# SensorPlatformV3.net
KiCad netlist of a schematic drawn in Altium Designer
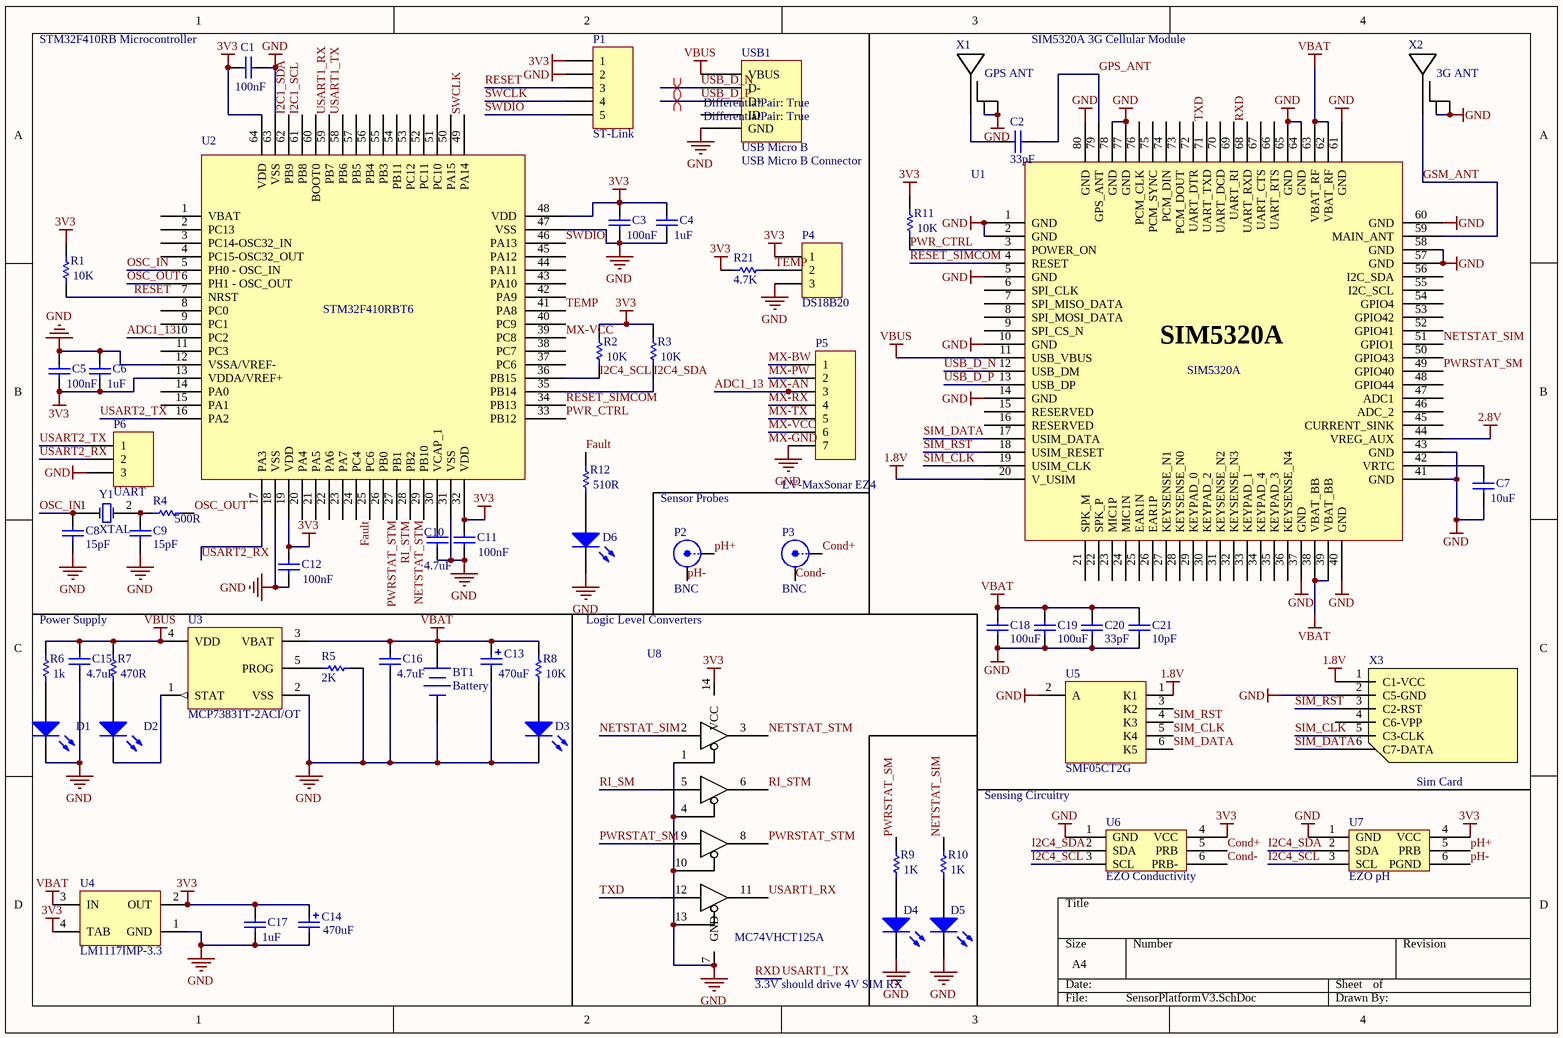
[diagram p0: SensorPlatformV3.SchDoc]

(export (version "E")
  (design (tool "Eeschema 10.0.6"))
  (components
    (comp (ref "BT1")
      (value "Battery")
      (footprint "BAT-2")
      (description "Multicell Battery")
      (fields (field (name "PUBLISHER") "Altium Limited"))
      (libsource (lib "Miscellaneous Devices") (part "Battery"))
    )
    (comp (ref "C1")
      (value "100nF")
      (footprint "1608[0603]")
      (description "Capacitor")
      (fields (field (name "Comment") "Cap") (field (name "PUBLISHER") "Altium Limited"))
      (libsource (lib "Miscellaneous Devices") (part "Cap"))
    )
    (comp (ref "C2")
      (value "33pF")
      (footprint "1608[0603]")
      (description "Capacitor")
      (fields (field (name "Comment") "Cap") (field (name "PUBLISHER") "Altium Limited"))
      (libsource (lib "Miscellaneous Devices") (part "Cap"))
    )
    (comp (ref "C3")
      (value "100nF")
      (footprint "1608[0603]")
      (description "Capacitor")
      (fields (field (name "Comment") "Cap") (field (name "PUBLISHER") "Altium Limited"))
      (libsource (lib "Miscellaneous Devices") (part "Cap"))
    )
    (comp (ref "C4")
      (value "1uF")
      (footprint "1608[0603]")
      (description "Capacitor")
      (fields (field (name "Comment") "Cap") (field (name "PUBLISHER") "Altium Limited"))
      (libsource (lib "Miscellaneous Devices") (part "Cap"))
    )
    (comp (ref "C5")
      (value "100nF")
      (footprint "1608[0603]")
      (description "Capacitor")
      (fields (field (name "Comment") "Cap") (field (name "PUBLISHER") "Altium Limited"))
      (libsource (lib "Miscellaneous Devices") (part "Cap"))
    )
    (comp (ref "C6")
      (value "1uF")
      (footprint "1608[0603]")
      (description "Capacitor")
      (fields (field (name "Comment") "Cap") (field (name "PUBLISHER") "Altium Limited"))
      (libsource (lib "Miscellaneous Devices") (part "Cap"))
    )
    (comp (ref "C7")
      (value "10uF")
      (footprint "1608[0603]")
      (description "Capacitor")
      (fields (field (name "Comment") "Cap") (field (name "PUBLISHER") "Altium Limited"))
      (libsource (lib "Miscellaneous Devices") (part "Cap"))
    )
    (comp (ref "C8")
      (value "15pF")
      (footprint "1608[0603]")
      (description "Capacitor")
      (fields (field (name "Comment") "Cap") (field (name "PUBLISHER") "Altium Limited"))
      (libsource (lib "Miscellaneous Devices") (part "Cap"))
    )
    (comp (ref "C9")
      (value "15pF")
      (footprint "1608[0603]")
      (description "Capacitor")
      (fields (field (name "Comment") "Cap") (field (name "PUBLISHER") "Altium Limited"))
      (libsource (lib "Miscellaneous Devices") (part "Cap"))
    )
    (comp (ref "C10")
      (value "4.7uF")
      (footprint "1608[0603]")
      (description "Capacitor")
      (fields (field (name "Comment") "Cap") (field (name "PUBLISHER") "Altium Limited"))
      (libsource (lib "Miscellaneous Devices") (part "Cap"))
    )
    (comp (ref "C11")
      (value "100nF")
      (footprint "1608[0603]")
      (description "Capacitor")
      (fields (field (name "Comment") "Cap") (field (name "PUBLISHER") "Altium Limited"))
      (libsource (lib "Miscellaneous Devices") (part "Cap"))
    )
    (comp (ref "C12")
      (value "100nF")
      (footprint "1608[0603]")
      (description "Capacitor")
      (fields (field (name "Comment") "Cap") (field (name "PUBLISHER") "Altium Limited"))
      (libsource (lib "Miscellaneous Devices") (part "Cap"))
    )
    (comp (ref "C13")
      (value "470uF")
      (footprint "CAPAE9983X105M")
      (description "Polarized Capacitor (Axial)")
      (fields (field (name "Comment") "Cap Pol2") (field (name "PUBLISHER") "Altium Limited"))
      (libsource (lib "Miscellaneous Devices") (part "Cap Pol2"))
    )
    (comp (ref "C14")
      (value "470uF")
      (footprint "CAPAE9983X105M")
      (description "Polarized Capacitor (Axial)")
      (fields (field (name "Comment") "Cap Pol2") (field (name "PUBLISHER") "Altium Limited"))
      (libsource (lib "Miscellaneous Devices") (part "Cap Pol2"))
    )
    (comp (ref "C15")
      (value "4.7uF")
      (footprint "1608[0603]")
      (description "Capacitor")
      (fields (field (name "Comment") "Cap") (field (name "PUBLISHER") "Altium Limited"))
      (libsource (lib "Miscellaneous Devices") (part "Cap"))
    )
    (comp (ref "C16")
      (value "4.7uF")
      (footprint "1608[0603]")
      (description "Capacitor")
      (fields (field (name "Comment") "Cap") (field (name "PUBLISHER") "Altium Limited"))
      (libsource (lib "Miscellaneous Devices") (part "Cap"))
    )
    (comp (ref "C17")
      (value "1uF")
      (footprint "1608[0603]")
      (description "Capacitor")
      (fields (field (name "Comment") "Cap") (field (name "PUBLISHER") "Altium Limited"))
      (libsource (lib "Miscellaneous Devices") (part "Cap"))
    )
    (comp (ref "C18")
      (value "100uF")
      (footprint "1608[0603]")
      (description "Capacitor")
      (fields (field (name "Comment") "Cap") (field (name "PUBLISHER") "Altium Limited"))
      (libsource (lib "Miscellaneous Devices") (part "Cap"))
    )
    (comp (ref "C19")
      (value "100uF")
      (footprint "1608[0603]")
      (description "Capacitor")
      (fields (field (name "Comment") "Cap") (field (name "PUBLISHER") "Altium Limited"))
      (libsource (lib "Miscellaneous Devices") (part "Cap"))
    )
    (comp (ref "C20")
      (value "33pF")
      (footprint "1608[0603]")
      (description "Capacitor")
      (fields (field (name "Comment") "Cap") (field (name "PUBLISHER") "Altium Limited"))
      (libsource (lib "Miscellaneous Devices") (part "Cap"))
    )
    (comp (ref "C21")
      (value "10pF")
      (footprint "1608[0603]")
      (description "Capacitor")
      (fields (field (name "Comment") "Cap") (field (name "PUBLISHER") "Altium Limited"))
      (libsource (lib "Miscellaneous Devices") (part "Cap"))
    )
    (comp (ref "D1")
      (value "USB")
      (footprint "1608[0603]")
      (description "Typical INFRARED GaAs LED")
      (fields (field (name "PUBLISHER") "Altium Limited"))
      (libsource (lib "Miscellaneous Devices") (part "LED0"))
    )
    (comp (ref "D2")
      (value "Ch")
      (footprint "1608[0603]")
      (description "Typical INFRARED GaAs LED")
      (fields (field (name "PUBLISHER") "Altium Limited"))
      (libsource (lib "Miscellaneous Devices") (part "LED0"))
    )
    (comp (ref "D3")
      (value "Bt")
      (footprint "1608[0603]")
      (description "Typical INFRARED GaAs LED")
      (fields (field (name "PUBLISHER") "Altium Limited"))
      (libsource (lib "Miscellaneous Devices") (part "LED0"))
    )
    (comp (ref "D4")
      (value "PWRSTAT")
      (footprint "1608[0603]")
      (description "Typical INFRARED GaAs LED")
      (fields (field (name "PUBLISHER") "Altium Limited"))
      (libsource (lib "Miscellaneous Devices") (part "LED0"))
    )
    (comp (ref "D5")
      (value "NETSTAT")
      (footprint "1608[0603]")
      (description "Typical INFRARED GaAs LED")
      (fields (field (name "PUBLISHER") "Altium Limited"))
      (libsource (lib "Miscellaneous Devices") (part "LED0"))
    )
    (comp (ref "D6")
      (value "Fault")
      (footprint "1608[0603]")
      (description "Typical INFRARED GaAs LED")
      (fields (field (name "PUBLISHER") "Altium Limited"))
      (libsource (lib "Miscellaneous Devices") (part "LED0"))
    )
    (comp (ref "P1")
      (value "ST-Link")
      (footprint "HDR1X5")
      (description "Header, 5-Pin")
      (fields (field (name "PUBLISHER") "Altium Limited"))
      (libsource (lib "Miscellaneous Connectors") (part "Header 5"))
    )
    (comp (ref "P2")
      (value "BNC")
      (footprint "BNC Connector")
      (description "BNC Elbow Connector")
      (fields (field (name "PUBLISHER") "Altium Limited"))
      (libsource (lib "Miscellaneous Connectors") (part "BNC"))
    )
    (comp (ref "P3")
      (value "BNC")
      (footprint "BNC Connector")
      (description "BNC Elbow Connector")
      (fields (field (name "PUBLISHER") "Altium Limited"))
      (libsource (lib "Miscellaneous Connectors") (part "BNC"))
    )
    (comp (ref "P4")
      (value "DS18B20")
      (footprint "HDR1X3")
      (description "Header, 3-Pin")
      (fields (field (name "PUBLISHER") "Altium Limited"))
      (libsource (lib "Miscellaneous Connectors") (part "Header 3"))
    )
    (comp (ref "P5")
      (value "LV-MaxSonar EZ4")
      (footprint "HDR1X7")
      (description "Header, 7-Pin")
      (fields (field (name "PUBLISHER") "Altium Limited"))
      (libsource (lib "Miscellaneous Connectors") (part "Header 7"))
    )
    (comp (ref "P6")
      (value "UART")
      (footprint "HDR1X3")
      (description "Header, 3-Pin")
      (fields (field (name "PUBLISHER") "Altium Limited"))
      (libsource (lib "Miscellaneous Connectors") (part "Header 3"))
    )
    (comp (ref "R1")
      (value "10K")
      (footprint "1608[0603]")
      (description "Resistor")
      (fields (field (name "Comment") "Res1") (field (name "PUBLISHER") "Altium Limited"))
      (libsource (lib "Miscellaneous Devices") (part "Res1"))
    )
    (comp (ref "R2")
      (value "10K")
      (footprint "1608[0603]")
      (description "Resistor")
      (fields (field (name "Comment") "Res1") (field (name "PUBLISHER") "Altium Limited"))
      (libsource (lib "Miscellaneous Devices") (part "Res1"))
    )
    (comp (ref "R3")
      (value "10K")
      (footprint "1608[0603]")
      (description "Resistor")
      (fields (field (name "Comment") "Res1") (field (name "PUBLISHER") "Altium Limited"))
      (libsource (lib "Miscellaneous Devices") (part "Res1"))
    )
    (comp (ref "R4")
      (value "500R")
      (footprint "1608[0603]")
      (description "Resistor")
      (fields (field (name "Comment") "Res1") (field (name "PUBLISHER") "Altium Limited"))
      (libsource (lib "Miscellaneous Devices") (part "Res1"))
    )
    (comp (ref "R5")
      (value "2K")
      (footprint "1608[0603]")
      (description "Resistor")
      (fields (field (name "Comment") "Res1") (field (name "PUBLISHER") "Altium Limited"))
      (libsource (lib "Miscellaneous Devices") (part "Res1"))
    )
    (comp (ref "R6")
      (value "1k")
      (footprint "1608[0603]")
      (description "Resistor")
      (fields (field (name "Comment") "Res1") (field (name "PUBLISHER") "Altium Limited"))
      (libsource (lib "Miscellaneous Devices") (part "Res1"))
    )
    (comp (ref "R7")
      (value "470R")
      (footprint "1608[0603]")
      (description "Resistor")
      (fields (field (name "Comment") "Res1") (field (name "PUBLISHER") "Altium Limited"))
      (libsource (lib "Miscellaneous Devices") (part "Res1"))
    )
    (comp (ref "R8")
      (value "10K")
      (footprint "1608[0603]")
      (description "Resistor")
      (fields (field (name "Comment") "Res1") (field (name "PUBLISHER") "Altium Limited"))
      (libsource (lib "Miscellaneous Devices") (part "Res1"))
    )
    (comp (ref "R9")
      (value "1K")
      (footprint "1608[0603]")
      (description "Resistor")
      (fields (field (name "Comment") "Res1") (field (name "PUBLISHER") "Altium Limited"))
      (libsource (lib "Miscellaneous Devices") (part "Res1"))
    )
    (comp (ref "R10")
      (value "1K")
      (footprint "1608[0603]")
      (description "Resistor")
      (fields (field (name "Comment") "Res1") (field (name "PUBLISHER") "Altium Limited"))
      (libsource (lib "Miscellaneous Devices") (part "Res1"))
    )
    (comp (ref "R11")
      (value "10K")
      (footprint "1608[0603]")
      (description "Resistor")
      (fields (field (name "Comment") "Res1") (field (name "PUBLISHER") "Altium Limited"))
      (libsource (lib "Miscellaneous Devices") (part "Res1"))
    )
    (comp (ref "R12")
      (value "510R")
      (footprint "1608[0603]")
      (description "Resistor")
      (fields (field (name "Comment") "Res1") (field (name "PUBLISHER") "Altium Limited"))
      (libsource (lib "Miscellaneous Devices") (part "Res1"))
    )
    (comp (ref "R21")
      (value "4.7K")
      (footprint "1608[0603]")
      (description "Resistor")
      (fields (field (name "Comment") "Res1") (field (name "PUBLISHER") "Altium Limited"))
      (libsource (lib "Miscellaneous Devices") (part "Res1"))
    )
    (comp (ref "U1")
      (value "SIM5320A")
      (footprint "SIM5320A")
      (libsource (lib "WillsSchematicLibrary") (part "SIM5320A"))
    )
    (comp (ref "U2")
      (value "STM32F410RBT6")
      (footprint "STM32F410RBT6")
      (libsource (lib "WillsSchematicLibrary") (part "STM32F410RBT6"))
    )
    (comp (ref "U3")
      (value "MCP73831T-2ACI/OT")
      (footprint "SOT-23-OT5_N")
      (fields (field (name "MANUFACTURER") "Microchip"))
      (libsource (lib "Microchip Power Management Battery Management") (part "MCP73831T-2ACI/OT"))
    )
    (comp (ref "U4")
      (value "LM1117IMP-3.3")
      (footprint "MP04A_N")
      (description "800mA Low-Dropout Linear Regulator, 4-pin SOT-223")
      (fields (field (name "MANUFACTURER") "National Semiconductor"))
      (libsource (lib "National Semiconductor LDO") (part "LM1117IMP-3.3"))
    )
    (comp (ref "U5")
      (value "SMF05CT2G")
      (footprint "ONSC-SC70-6-419B-02_W_V")
      (description "5-Line Transient Voltage Suppressor Array, 6-Pin SC70, Pb-Free, Tape and Reel")
      (fields (field (name "MANUFACTURER") "On Semiconductor"))
      (libsource (lib "ON Semi Transient Voltage Suppressors (TVS)") (part "SMF05CT2G"))
    )
    (comp (ref "U6")
      (value "EZO Conductivity")
      (footprint "EZO Conductivity (No Writing)")
      (libsource (lib "WillsSchematicLibrary") (part "EZO Conductivity"))
    )
    (comp (ref "U7")
      (value "EZO pH")
      (footprint "EZO pH Duplicate")
      (libsource (lib "WillsSchematicLibrary") (part "EZO pH"))
    )
    (comp (ref "U8")
      (value "MC74VHCT125A")
      (footprint "TSSOP-14")
      (libsource (lib "WillsSchematicLibrary") (part "MC74VHCT125A"))
    )
    (comp (ref "USB1")
      (value "USB Micro B Connector")
      (footprint "USB Micro B Connector")
      (libsource (lib "WillsSchematicLibrary") (part "USB Micro B Connector"))
    )
    (comp (ref "X1")
      (value "GPS ANT")
      (footprint "UFL Connector")
      (libsource (lib "WillsSchematicLibrary") (part "UFL Antenna"))
    )
    (comp (ref "X2")
      (value "3G ANT")
      (footprint "UFL Connector")
      (libsource (lib "WillsSchematicLibrary") (part "UFL Antenna"))
    )
    (comp (ref "X3")
      (value "Sim Card")
      (footprint "Sim Card")
      (libsource (lib "WillsSchematicLibrary") (part "SIMCARD"))
    )
    (comp (ref "Y1")
      (value "XTAL")
      (footprint "16MHz Clock")
      (description "Crystal Oscillator")
      (fields (field (name "PUBLISHER") "Altium Limited"))
      (libsource (lib "Miscellaneous Devices") (part "XTAL"))
    )
  )
  (nets
    (net (code "1") (name "/ADC1_13") (class "Default")
      (node (ref "P5") (pin "3") (pinfunction "3_3") (pintype "passive"))
      (node (ref "U2") (pin "10") (pinfunction "PC2_10") (pintype "passive"))
    )
    (net (code "2") (name "/Cond+") (class "Default")
      (node (ref "P3") (pin "1") (pinfunction "X_1") (pintype "passive"))
      (node (ref "U6") (pin "5") (pinfunction "PRB_5") (pintype "passive"))
    )
    (net (code "3") (name "/Cond-") (class "Default")
      (node (ref "P3") (pin "2") (pinfunction "Y_2") (pintype "passive"))
      (node (ref "U6") (pin "6") (pinfunction "PRB-_6") (pintype "passive"))
    )
    (net (code "4") (name "/Fault") (class "Default")
      (node (ref "R12") (pin "2") (pinfunction "2_2") (pintype "passive"))
      (node (ref "U2") (pin "24") (pinfunction "PC4_24") (pintype "passive"))
    )
    (net (code "5") (name "/GPS_ANT") (class "Default")
      (node (ref "C2") (pin "1") (pinfunction "1_1") (pintype "passive"))
      (node (ref "U1") (pin "79") (pinfunction "GPS_ANT_79") (pintype "passive"))
    )
    (net (code "6") (name "/GSM_ANT") (class "Default")
      (node (ref "U1") (pin "59") (pinfunction "MAIN_ANT_59") (pintype "passive"))
      (node (ref "X2") (pin "1") (pinfunction "SIG_1") (pintype "passive"))
    )
    (net (code "7") (name "/I2C1_SCL") (class "Default")
      (node (ref "U2") (pin "61") (pinfunction "PB8_61") (pintype "passive"))
    )
    (net (code "8") (name "/I2C1_SDA") (class "Default")
      (node (ref "U2") (pin "62") (pinfunction "PB9_62") (pintype "passive"))
    )
    (net (code "9") (name "/I2C4_SCL") (class "Default")
      (node (ref "R2") (pin "1") (pinfunction "1_1") (pintype "passive"))
      (node (ref "U2") (pin "36") (pinfunction "PB15_36") (pintype "passive"))
      (node (ref "U6") (pin "3") (pinfunction "SCL_3") (pintype "passive"))
      (node (ref "U7") (pin "3") (pinfunction "SCL_3") (pintype "passive"))
    )
    (net (code "10") (name "/I2C4_SDA") (class "Default")
      (node (ref "R3") (pin "1") (pinfunction "1_1") (pintype "passive"))
      (node (ref "U2") (pin "35") (pinfunction "PB14_35") (pintype "passive"))
      (node (ref "U6") (pin "2") (pinfunction "SDA_2") (pintype "passive"))
      (node (ref "U7") (pin "2") (pinfunction "SDA_2") (pintype "passive"))
    )
    (net (code "11") (name "/MX-BW") (class "Default")
      (node (ref "P5") (pin "1") (pinfunction "1_1") (pintype "passive"))
    )
    (net (code "13") (name "/MX-PW") (class "Default")
      (node (ref "P5") (pin "2") (pinfunction "2_2") (pintype "passive"))
    )
    (net (code "14") (name "/MX-RX") (class "Default")
      (node (ref "P5") (pin "4") (pinfunction "4_4") (pintype "passive"))
    )
    (net (code "15") (name "/MX-TX") (class "Default")
      (node (ref "P5") (pin "5") (pinfunction "5_5") (pintype "passive"))
    )
    (net (code "16") (name "/MX-VCC") (class "Default")
      (node (ref "P5") (pin "6") (pinfunction "6_6") (pintype "passive"))
      (node (ref "U2") (pin "39") (pinfunction "PC8_39") (pintype "passive"))
    )
    (net (code "17") (name "/NETSTAT_SIM") (class "Default")
      (node (ref "R10") (pin "2") (pinfunction "2_2") (pintype "passive"))
      (node (ref "U1") (pin "51") (pinfunction "GPIO1_51") (pintype "passive"))
      (node (ref "U8") (pin "2") (pinfunction "A1_2") (pintype "passive"))
    )
    (net (code "18") (name "/NETSTAT_STM") (class "Default")
      (node (ref "U2") (pin "28") (pinfunction "PB2_28") (pintype "passive"))
      (node (ref "U8") (pin "3") (pinfunction "Y1_3") (pintype "passive"))
    )
    (net (code "19") (name "/OSC_IN") (class "Default")
      (node (ref "C8") (pin "1") (pinfunction "1_1") (pintype "passive"))
      (node (ref "U2") (pin "5") (pinfunction "PH0_-_OSC_IN_5") (pintype "passive"))
      (node (ref "Y1") (pin "1") (pinfunction "OSC1_1") (pintype "passive"))
    )
    (net (code "20") (name "/OSC_OUT") (class "Default")
      (node (ref "R4") (pin "1") (pinfunction "1_1") (pintype "passive"))
      (node (ref "U2") (pin "6") (pinfunction "PH1_-_OSC_OUT_6") (pintype "passive"))
    )
    (net (code "21") (name "/PWRSTAT_SM") (class "Default")
      (node (ref "R9") (pin "2") (pinfunction "2_2") (pintype "passive"))
      (node (ref "U1") (pin "49") (pinfunction "GPIO40_49") (pintype "passive"))
      (node (ref "U8") (pin "9") (pinfunction "A3_9") (pintype "passive"))
    )
    (net (code "22") (name "/PWRSTAT_STM") (class "Default")
      (node (ref "U2") (pin "26") (pinfunction "PB0_26") (pintype "passive"))
      (node (ref "U8") (pin "8") (pinfunction "U4_8") (pintype "passive"))
    )
    (net (code "23") (name "/PWR_CTRL") (class "Default")
      (node (ref "R11") (pin "1") (pinfunction "1_1") (pintype "passive"))
      (node (ref "U1") (pin "3") (pinfunction "POWER_ON_3") (pintype "passive"))
      (node (ref "U2") (pin "33") (pinfunction "PB12_33") (pintype "passive"))
    )
    (net (code "24") (name "/RESET") (class "Default")
      (node (ref "P1") (pin "3") (pinfunction "3_3") (pintype "passive"))
      (node (ref "R1") (pin "1") (pinfunction "1_1") (pintype "passive"))
      (node (ref "U2") (pin "7") (pinfunction "NRST_7") (pintype "passive"))
    )
    (net (code "25") (name "/RESET_SIMCOM") (class "Default")
      (node (ref "U1") (pin "4") (pinfunction "RESET_4") (pintype "passive"))
      (node (ref "U2") (pin "34") (pinfunction "PB13_34") (pintype "passive"))
    )
    (net (code "26") (name "/RI_SM") (class "Default")
      (node (ref "U8") (pin "5") (pinfunction "A2_5") (pintype "passive"))
    )
    (net (code "27") (name "/RI_STM") (class "Default")
      (node (ref "U2") (pin "27") (pinfunction "PB1_27") (pintype "passive"))
      (node (ref "U8") (pin "6") (pinfunction "Y2_6") (pintype "passive"))
    )
    (net (code "28") (name "/RXD") (class "Default")
      (node (ref "U1") (pin "68") (pinfunction "UART_RXD_68") (pintype "passive"))
      (node (ref "U2") (pin "58") (pinfunction "PB6_58") (pintype "passive"))
    )
    (net (code "29") (name "/SIM_CLK") (class "Default")
      (node (ref "U1") (pin "19") (pinfunction "USIM_CLK_19") (pintype "passive"))
      (node (ref "U5") (pin "5") (pinfunction "K4_5") (pintype "passive"))
      (node (ref "X3") (pin "5") (pinfunction "C3-CLK_5") (pintype "passive"))
    )
    (net (code "30") (name "/SIM_DATA") (class "Default")
      (node (ref "U1") (pin "17") (pinfunction "USIM_DATA_17") (pintype "passive"))
      (node (ref "U5") (pin "6") (pinfunction "K5_6") (pintype "passive"))
      (node (ref "X3") (pin "6") (pinfunction "C7-DATA_6") (pintype "passive"))
    )
    (net (code "31") (name "/SIM_RST") (class "Default")
      (node (ref "U1") (pin "18") (pinfunction "USIM_RESET_18") (pintype "passive"))
      (node (ref "U5") (pin "4") (pinfunction "K3_4") (pintype "passive"))
      (node (ref "X3") (pin "3") (pinfunction "C2-RST_3") (pintype "passive"))
    )
    (net (code "32") (name "/SWCLK") (class "Default")
      (node (ref "P1") (pin "4") (pinfunction "4_4") (pintype "passive"))
      (node (ref "U2") (pin "49") (pinfunction "PA14_49") (pintype "passive"))
    )
    (net (code "33") (name "/SWDIO") (class "Default")
      (node (ref "P1") (pin "5") (pinfunction "5_5") (pintype "passive"))
      (node (ref "U2") (pin "46") (pinfunction "PA13_46") (pintype "passive"))
    )
    (net (code "34") (name "/TEMP") (class "Default")
      (node (ref "P4") (pin "2") (pinfunction "2_2") (pintype "passive"))
      (node (ref "R21") (pin "1") (pinfunction "1_1") (pintype "passive"))
      (node (ref "U2") (pin "41") (pinfunction "PA8_41") (pintype "passive"))
    )
    (net (code "35") (name "/TXD") (class "Default")
      (node (ref "U1") (pin "71") (pinfunction "UART_TXD_71") (pintype "passive"))
      (node (ref "U8") (pin "12") (pinfunction "A4_12") (pintype "passive"))
    )
    (net (code "36") (name "/USART1_RX") (class "Default")
      (node (ref "U2") (pin "59") (pinfunction "PB7_59") (pintype "passive"))
      (node (ref "U8") (pin "11") (pinfunction "Y4_11") (pintype "passive"))
    )
    (net (code "37") (name "/USART2_RX") (class "Default")
      (node (ref "P6") (pin "2") (pinfunction "2_2") (pintype "passive"))
      (node (ref "U2") (pin "17") (pinfunction "PA3_17") (pintype "passive"))
    )
    (net (code "38") (name "/USART2_TX") (class "Default")
      (node (ref "P6") (pin "1") (pinfunction "1_1") (pintype "passive"))
      (node (ref "U2") (pin "16") (pinfunction "PA2_16") (pintype "passive"))
    )
    (net (code "39") (name "/USB_D_N") (class "Default")
      (node (ref "U1") (pin "12") (pinfunction "USB_DM_12") (pintype "passive"))
      (node (ref "USB1") (pin "D-") (pinfunction "D-_D-") (pintype "passive"))
    )
    (net (code "40") (name "/USB_D_P") (class "Default")
      (node (ref "U1") (pin "13") (pinfunction "USB_DP_13") (pintype "passive"))
      (node (ref "USB1") (pin "D+") (pinfunction "D+_D+") (pintype "passive"))
    )
    (net (code "41") (name "/pH+") (class "Default")
      (node (ref "P2") (pin "1") (pinfunction "X_1") (pintype "passive"))
      (node (ref "U7") (pin "5") (pinfunction "PRB_5") (pintype "passive"))
    )
    (net (code "42") (name "/pH-") (class "Default")
      (node (ref "P2") (pin "2") (pinfunction "Y_2") (pintype "passive"))
      (node (ref "U7") (pin "6") (pinfunction "PGND_6") (pintype "passive"))
    )
    (net (code "43") (name "1.8V") (class "Default")
      (node (ref "U1") (pin "20") (pinfunction "V_USIM_20") (pintype "passive"))
      (node (ref "U5") (pin "1") (pinfunction "K1_1") (pintype "passive"))
      (node (ref "X3") (pin "1") (pinfunction "C1-VCC_1") (pintype "passive"))
    )
    (net (code "44") (name "2.8V") (class "Default")
      (node (ref "U1") (pin "44") (pinfunction "VREG_AUX_44") (pintype "passive"))
    )
    (net (code "45") (name "3V3") (class "Default")
      (node (ref "C1") (pin "2") (pinfunction "2_2") (pintype "passive"))
      (node (ref "C11") (pin "2") (pinfunction "2_2") (pintype "passive"))
      (node (ref "C12") (pin "2") (pinfunction "2_2") (pintype "passive"))
      (node (ref "C14") (pin "1") (pinfunction "1_1") (pintype "passive"))
      (node (ref "C17") (pin "2") (pinfunction "2_2") (pintype "passive"))
      (node (ref "C3") (pin "2") (pinfunction "2_2") (pintype "passive"))
      (node (ref "C4") (pin "2") (pinfunction "2_2") (pintype "passive"))
      (node (ref "C5") (pin "1") (pinfunction "1_1") (pintype "passive"))
      (node (ref "C6") (pin "1") (pinfunction "1_1") (pintype "passive"))
      (node (ref "P1") (pin "1") (pinfunction "1_1") (pintype "passive"))
      (node (ref "P4") (pin "1") (pinfunction "1_1") (pintype "passive"))
      (node (ref "R1") (pin "2") (pinfunction "2_2") (pintype "passive"))
      (node (ref "R11") (pin "2") (pinfunction "2_2") (pintype "passive"))
      (node (ref "R2") (pin "2") (pinfunction "2_2") (pintype "passive"))
      (node (ref "R21") (pin "2") (pinfunction "2_2") (pintype "passive"))
      (node (ref "R3") (pin "2") (pinfunction "2_2") (pintype "passive"))
      (node (ref "U2") (pin "13") (pinfunction "VDDA/VREF+_13") (pintype "passive"))
      (node (ref "U2") (pin "19") (pinfunction "VDD_19") (pintype "passive"))
      (node (ref "U2") (pin "32") (pinfunction "VDD_32") (pintype "passive"))
      (node (ref "U2") (pin "48") (pinfunction "VDD_48") (pintype "passive"))
      (node (ref "U2") (pin "64") (pinfunction "VDD_64") (pintype "passive"))
      (node (ref "U4") (pin "2") (pinfunction "OUT_2") (pintype "power_in"))
      (node (ref "U4") (pin "4") (pinfunction "TAB_4") (pintype "power_in"))
      (node (ref "U6") (pin "4") (pinfunction "VCC_4") (pintype "passive"))
      (node (ref "U7") (pin "4") (pinfunction "VCC_4") (pintype "passive"))
      (node (ref "U8") (pin "14") (pinfunction "VCC_14") (pintype "passive"))
    )
    (net (code "46") (name "GND") (class "Default")
      (node (ref "BT1") (pin "2") (pinfunction "-_2") (pintype "passive"))
      (node (ref "C1") (pin "1") (pinfunction "1_1") (pintype "passive"))
      (node (ref "C10") (pin "1") (pinfunction "1_1") (pintype "passive"))
      (node (ref "C11") (pin "1") (pinfunction "1_1") (pintype "passive"))
      (node (ref "C12") (pin "1") (pinfunction "1_1") (pintype "passive"))
      (node (ref "C13") (pin "2") (pinfunction "2_2") (pintype "passive"))
      (node (ref "C14") (pin "2") (pinfunction "2_2") (pintype "passive"))
      (node (ref "C15") (pin "1") (pinfunction "1_1") (pintype "passive"))
      (node (ref "C16") (pin "1") (pinfunction "1_1") (pintype "passive"))
      (node (ref "C17") (pin "1") (pinfunction "1_1") (pintype "passive"))
      (node (ref "C18") (pin "2") (pinfunction "2_2") (pintype "passive"))
      (node (ref "C19") (pin "2") (pinfunction "2_2") (pintype "passive"))
      (node (ref "C20") (pin "2") (pinfunction "2_2") (pintype "passive"))
      (node (ref "C21") (pin "2") (pinfunction "2_2") (pintype "passive"))
      (node (ref "C3") (pin "1") (pinfunction "1_1") (pintype "passive"))
      (node (ref "C4") (pin "1") (pinfunction "1_1") (pintype "passive"))
      (node (ref "C5") (pin "2") (pinfunction "2_2") (pintype "passive"))
      (node (ref "C6") (pin "2") (pinfunction "2_2") (pintype "passive"))
      (node (ref "C7") (pin "1") (pinfunction "1_1") (pintype "passive"))
      (node (ref "C8") (pin "2") (pinfunction "2_2") (pintype "passive"))
      (node (ref "C9") (pin "2") (pinfunction "2_2") (pintype "passive"))
      (node (ref "D1") (pin "2") (pinfunction "K_2") (pintype "passive"))
      (node (ref "D3") (pin "2") (pinfunction "K_2") (pintype "passive"))
      (node (ref "D4") (pin "2") (pinfunction "K_2") (pintype "passive"))
      (node (ref "D5") (pin "2") (pinfunction "K_2") (pintype "passive"))
      (node (ref "D6") (pin "2") (pinfunction "K_2") (pintype "passive"))
      (node (ref "P1") (pin "2") (pinfunction "2_2") (pintype "passive"))
      (node (ref "P4") (pin "3") (pinfunction "3_3") (pintype "passive"))
      (node (ref "P5") (pin "7") (pinfunction "7_7") (pintype "passive"))
      (node (ref "P6") (pin "3") (pinfunction "3_3") (pintype "passive"))
      (node (ref "R5") (pin "1") (pinfunction "1_1") (pintype "passive"))
      (node (ref "U1") (pin "1") (pinfunction "GND_1") (pintype "passive"))
      (node (ref "U1") (pin "10") (pinfunction "GND_10") (pintype "passive"))
      (node (ref "U1") (pin "14") (pinfunction "GND_14") (pintype "passive"))
      (node (ref "U1") (pin "2") (pinfunction "GND_2") (pintype "passive"))
      (node (ref "U1") (pin "37") (pinfunction "GND_37") (pintype "passive"))
      (node (ref "U1") (pin "40") (pinfunction "GND_40") (pintype "passive"))
      (node (ref "U1") (pin "41") (pinfunction "GND_41") (pintype "passive"))
      (node (ref "U1") (pin "43") (pinfunction "GND_43") (pintype "passive"))
      (node (ref "U1") (pin "5") (pinfunction "GND_5") (pintype "passive"))
      (node (ref "U1") (pin "57") (pinfunction "GND_57") (pintype "passive"))
      (node (ref "U1") (pin "58") (pinfunction "GND_58") (pintype "passive"))
      (node (ref "U1") (pin "60") (pinfunction "GND_60") (pintype "passive"))
      (node (ref "U1") (pin "61") (pinfunction "GND_61") (pintype "passive"))
      (node (ref "U1") (pin "64") (pinfunction "GND_64") (pintype "passive"))
      (node (ref "U1") (pin "65") (pinfunction "GND_65") (pintype "passive"))
      (node (ref "U1") (pin "77") (pinfunction "GND_77") (pintype "passive"))
      (node (ref "U1") (pin "78") (pinfunction "GND_78") (pintype "passive"))
      (node (ref "U1") (pin "80") (pinfunction "GND_80") (pintype "passive"))
      (node (ref "U2") (pin "12") (pinfunction "VSSA/VREF-_12") (pintype "passive"))
      (node (ref "U2") (pin "18") (pinfunction "VSS_18") (pintype "passive"))
      (node (ref "U2") (pin "31") (pinfunction "VSS_31") (pintype "passive"))
      (node (ref "U2") (pin "47") (pinfunction "VSS_47") (pintype "passive"))
      (node (ref "U2") (pin "63") (pinfunction "VSS_63") (pintype "passive"))
      (node (ref "U3") (pin "2") (pinfunction "VSS_2") (pintype "power_in"))
      (node (ref "U4") (pin "1") (pinfunction "GND_1") (pintype "power_in"))
      (node (ref "U5") (pin "2") (pinfunction "A_2") (pintype "passive"))
      (node (ref "U6") (pin "1") (pinfunction "GND_1") (pintype "passive"))
      (node (ref "U7") (pin "1") (pinfunction "GND_1") (pintype "passive"))
      (node (ref "U8") (pin "1") (pinfunction "OE1_1") (pintype "passive"))
      (node (ref "U8") (pin "10") (pinfunction "OE3_10") (pintype "passive"))
      (node (ref "U8") (pin "13") (pinfunction "OE4_13") (pintype "passive"))
      (node (ref "U8") (pin "4") (pinfunction "OE2_4") (pintype "passive"))
      (node (ref "U8") (pin "7") (pinfunction "GND_7") (pintype "passive"))
      (node (ref "USB1") (pin "GND") (pinfunction "GND_GND") (pintype "passive"))
      (node (ref "X1") (pin "2") (pinfunction "GND_2") (pintype "passive"))
      (node (ref "X1") (pin "3") (pinfunction "GND_3") (pintype "passive"))
      (node (ref "X2") (pin "2") (pinfunction "GND_2") (pintype "passive"))
      (node (ref "X2") (pin "3") (pinfunction "GND_3") (pintype "passive"))
      (node (ref "X3") (pin "2") (pinfunction "C5-GND_2") (pintype "passive"))
    )
    (net (code "47") (name "Net-(D1-A)") (class "Default")
      (node (ref "D1") (pin "1") (pinfunction "A_1") (pintype "passive"))
      (node (ref "R6") (pin "1") (pinfunction "1_1") (pintype "passive"))
    )
    (net (code "48") (name "Net-(D2-A)") (class "Default")
      (node (ref "D2") (pin "1") (pinfunction "A_1") (pintype "passive"))
      (node (ref "R7") (pin "1") (pinfunction "1_1") (pintype "passive"))
    )
    (net (code "49") (name "Net-(D2-K)") (class "Default")
      (node (ref "D2") (pin "2") (pinfunction "K_2") (pintype "passive"))
      (node (ref "U3") (pin "1") (pinfunction "STAT_1") (pintype "output"))
    )
    (net (code "50") (name "Net-(D3-A)") (class "Default")
      (node (ref "D3") (pin "1") (pinfunction "A_1") (pintype "passive"))
      (node (ref "R8") (pin "1") (pinfunction "1_1") (pintype "passive"))
    )
    (net (code "51") (name "Net-(D4-A)") (class "Default")
      (node (ref "D4") (pin "1") (pinfunction "A_1") (pintype "passive"))
      (node (ref "R9") (pin "1") (pinfunction "1_1") (pintype "passive"))
    )
    (net (code "52") (name "Net-(D5-A)") (class "Default")
      (node (ref "D5") (pin "1") (pinfunction "A_1") (pintype "passive"))
      (node (ref "R10") (pin "1") (pinfunction "1_1") (pintype "passive"))
    )
    (net (code "53") (name "Net-(D6-A)") (class "Default")
      (node (ref "D6") (pin "1") (pinfunction "A_1") (pintype "passive"))
      (node (ref "R12") (pin "1") (pinfunction "1_1") (pintype "passive"))
    )
    (net (code "54") (name "Net-(U1-VRTC)") (class "Default")
      (node (ref "C7") (pin "2") (pinfunction "2_2") (pintype "passive"))
      (node (ref "U1") (pin "42") (pinfunction "VRTC_42") (pintype "passive"))
    )
    (net (code "55") (name "Net-(U2-VCAP_1)") (class "Default")
      (node (ref "C10") (pin "2") (pinfunction "2_2") (pintype "passive"))
      (node (ref "U2") (pin "30") (pinfunction "VCAP_1_30") (pintype "passive"))
    )
    (net (code "56") (name "Net-(U3-PROG)") (class "Default")
      (node (ref "R5") (pin "2") (pinfunction "2_2") (pintype "passive"))
      (node (ref "U3") (pin "5") (pinfunction "PROG_5") (pintype "passive"))
    )
    (net (code "57") (name "Net-(X1-SIG)") (class "Default")
      (node (ref "C2") (pin "2") (pinfunction "2_2") (pintype "passive"))
      (node (ref "X1") (pin "1") (pinfunction "SIG_1") (pintype "passive"))
    )
    (net (code "58") (name "Net-(Y1-OSC2)") (class "Default")
      (node (ref "C9") (pin "1") (pinfunction "1_1") (pintype "passive"))
      (node (ref "R4") (pin "2") (pinfunction "2_2") (pintype "passive"))
      (node (ref "Y1") (pin "2") (pinfunction "OSC2_2") (pintype "passive"))
    )
    (net (code "59") (name "VBAT") (class "Default")
      (node (ref "BT1") (pin "1") (pinfunction "+_1") (pintype "passive"))
      (node (ref "C13") (pin "1") (pinfunction "1_1") (pintype "passive"))
      (node (ref "C16") (pin "2") (pinfunction "2_2") (pintype "passive"))
      (node (ref "C18") (pin "1") (pinfunction "1_1") (pintype "passive"))
      (node (ref "C19") (pin "1") (pinfunction "1_1") (pintype "passive"))
      (node (ref "C20") (pin "1") (pinfunction "1_1") (pintype "passive"))
      (node (ref "C21") (pin "1") (pinfunction "1_1") (pintype "passive"))
      (node (ref "R8") (pin "2") (pinfunction "2_2") (pintype "passive"))
      (node (ref "U1") (pin "38") (pinfunction "VBAT_BB_38") (pintype "passive"))
      (node (ref "U1") (pin "39") (pinfunction "VBAT_BB_39") (pintype "passive"))
      (node (ref "U1") (pin "62") (pinfunction "VBAT_RF_62") (pintype "passive"))
      (node (ref "U1") (pin "63") (pinfunction "VBAT_RF_63") (pintype "passive"))
      (node (ref "U3") (pin "3") (pinfunction "VBAT_3") (pintype "power_in"))
      (node (ref "U4") (pin "3") (pinfunction "IN_3") (pintype "power_in"))
    )
    (net (code "60") (name "VBUS") (class "Default")
      (node (ref "C15") (pin "2") (pinfunction "2_2") (pintype "passive"))
      (node (ref "R6") (pin "2") (pinfunction "2_2") (pintype "passive"))
      (node (ref "R7") (pin "2") (pinfunction "2_2") (pintype "passive"))
      (node (ref "U1") (pin "11") (pinfunction "USB_VBUS_11") (pintype "passive"))
      (node (ref "U3") (pin "4") (pinfunction "VDD_4") (pintype "power_in"))
      (node (ref "USB1") (pin "VBUS") (pinfunction "VBUS_VBUS") (pintype "passive"))
    )
    (net (code "61") (name "unconnected-(U1-ADC1-Pad47)") (class "Default")
      (node (ref "U1") (pin "47") (pinfunction "ADC1_47") (pintype "passive"))
    )
    (net (code "62") (name "unconnected-(U1-ADC_2-Pad46)") (class "Default")
      (node (ref "U1") (pin "46") (pinfunction "ADC_2_46") (pintype "passive"))
    )
    (net (code "63") (name "unconnected-(U1-CURRENT_SINK-Pad45)") (class "Default")
      (node (ref "U1") (pin "45") (pinfunction "CURRENT_SINK_45") (pintype "passive"))
    )
    (net (code "64") (name "unconnected-(U1-EAR1N-Pad25)") (class "Default")
      (node (ref "U1") (pin "25") (pinfunction "EAR1N_25") (pintype "passive"))
    )
    (net (code "65") (name "unconnected-(U1-EAR1P-Pad26)") (class "Default")
      (node (ref "U1") (pin "26") (pinfunction "EAR1P_26") (pintype "passive"))
    )
    (net (code "66") (name "unconnected-(U1-GPIO4-Pad54)") (class "Default")
      (node (ref "U1") (pin "54") (pinfunction "GPIO4_54") (pintype "passive"))
    )
    (net (code "67") (name "unconnected-(U1-GPIO41-Pad52)") (class "Default")
      (node (ref "U1") (pin "52") (pinfunction "GPIO41_52") (pintype "passive"))
    )
    (net (code "68") (name "unconnected-(U1-GPIO42-Pad53)") (class "Default")
      (node (ref "U1") (pin "53") (pinfunction "GPIO42_53") (pintype "passive"))
    )
    (net (code "69") (name "unconnected-(U1-GPIO43-Pad50)") (class "Default")
      (node (ref "U1") (pin "50") (pinfunction "GPIO43_50") (pintype "passive"))
    )
    (net (code "70") (name "unconnected-(U1-GPIO44-Pad48)") (class "Default")
      (node (ref "U1") (pin "48") (pinfunction "GPIO44_48") (pintype "passive"))
    )
    (net (code "71") (name "unconnected-(U1-I2C_SCL-Pad55)") (class "Default")
      (node (ref "U1") (pin "55") (pinfunction "I2C_SCL_55") (pintype "passive"))
    )
    (net (code "72") (name "unconnected-(U1-I2C_SDA-Pad56)") (class "Default")
      (node (ref "U1") (pin "56") (pinfunction "I2C_SDA_56") (pintype "passive"))
    )
    (net (code "73") (name "unconnected-(U1-KEYPAD_0-Pad29)") (class "Default")
      (node (ref "U1") (pin "29") (pinfunction "KEYPAD_0_29") (pintype "passive"))
    )
    (net (code "74") (name "unconnected-(U1-KEYPAD_1-Pad33)") (class "Default")
      (node (ref "U1") (pin "33") (pinfunction "KEYPAD_1_33") (pintype "passive"))
    )
    (net (code "75") (name "unconnected-(U1-KEYPAD_2-Pad30)") (class "Default")
      (node (ref "U1") (pin "30") (pinfunction "KEYPAD_2_30") (pintype "passive"))
    )
    (net (code "76") (name "unconnected-(U1-KEYPAD_3-Pad35)") (class "Default")
      (node (ref "U1") (pin "35") (pinfunction "KEYPAD_3_35") (pintype "passive"))
    )
    (net (code "77") (name "unconnected-(U1-KEYPAD_4-Pad34)") (class "Default")
      (node (ref "U1") (pin "34") (pinfunction "KEYPAD_4_34") (pintype "passive"))
    )
    (net (code "78") (name "unconnected-(U1-KEYSENSE_N0-Pad28)") (class "Default")
      (node (ref "U1") (pin "28") (pinfunction "KEYSENSE_N0_28") (pintype "passive"))
    )
    (net (code "79") (name "unconnected-(U1-KEYSENSE_N1-Pad27)") (class "Default")
      (node (ref "U1") (pin "27") (pinfunction "KEYSENSE_N1_27") (pintype "passive"))
    )
    (net (code "80") (name "unconnected-(U1-KEYSENSE_N2-Pad31)") (class "Default")
      (node (ref "U1") (pin "31") (pinfunction "KEYSENSE_N2_31") (pintype "passive"))
    )
    (net (code "81") (name "unconnected-(U1-KEYSENSE_N3-Pad32)") (class "Default")
      (node (ref "U1") (pin "32") (pinfunction "KEYSENSE_N3_32") (pintype "passive"))
    )
    (net (code "82") (name "unconnected-(U1-KEYSENSE_N4-Pad36)") (class "Default")
      (node (ref "U1") (pin "36") (pinfunction "KEYSENSE_N4_36") (pintype "passive"))
    )
    (net (code "83") (name "unconnected-(U1-MIC1N-Pad24)") (class "Default")
      (node (ref "U1") (pin "24") (pinfunction "MIC1N_24") (pintype "passive"))
    )
    (net (code "84") (name "unconnected-(U1-MIC1P-Pad23)") (class "Default")
      (node (ref "U1") (pin "23") (pinfunction "MIC1P_23") (pintype "passive"))
    )
    (net (code "85") (name "unconnected-(U1-PCM_CLK-Pad76)") (class "Default")
      (node (ref "U1") (pin "76") (pinfunction "PCM_CLK_76") (pintype "passive"))
    )
    (net (code "86") (name "unconnected-(U1-PCM_DIN-Pad74)") (class "Default")
      (node (ref "U1") (pin "74") (pinfunction "PCM_DIN_74") (pintype "passive"))
    )
    (net (code "87") (name "unconnected-(U1-PCM_DOUT-Pad73)") (class "Default")
      (node (ref "U1") (pin "73") (pinfunction "PCM_DOUT_73") (pintype "passive"))
    )
    (net (code "88") (name "unconnected-(U1-PCM_SYNC-Pad75)") (class "Default")
      (node (ref "U1") (pin "75") (pinfunction "PCM_SYNC_75") (pintype "passive"))
    )
    (net (code "89") (name "unconnected-(U1-RESERVED-Pad15)") (class "Default")
      (node (ref "U1") (pin "15") (pinfunction "RESERVED_15") (pintype "passive"))
    )
    (net (code "90") (name "unconnected-(U1-RESERVED-Pad16)") (class "Default")
      (node (ref "U1") (pin "16") (pinfunction "RESERVED_16") (pintype "passive"))
    )
    (net (code "91") (name "unconnected-(U1-SPI_CLK-Pad6)") (class "Default")
      (node (ref "U1") (pin "6") (pinfunction "SPI_CLK_6") (pintype "passive"))
    )
    (net (code "92") (name "unconnected-(U1-SPI_CS_N-Pad9)") (class "Default")
      (node (ref "U1") (pin "9") (pinfunction "SPI_CS_N_9") (pintype "passive"))
    )
    (net (code "93") (name "unconnected-(U1-SPI_MISO_DATA-Pad7)") (class "Default")
      (node (ref "U1") (pin "7") (pinfunction "SPI_MISO_DATA_7") (pintype "passive"))
    )
    (net (code "94") (name "unconnected-(U1-SPI_MOSI_DATA-Pad8)") (class "Default")
      (node (ref "U1") (pin "8") (pinfunction "SPI_MOSI_DATA_8") (pintype "passive"))
    )
    (net (code "95") (name "unconnected-(U1-SPK_M-Pad21)") (class "Default")
      (node (ref "U1") (pin "21") (pinfunction "SPK_M_21") (pintype "passive"))
    )
    (net (code "96") (name "unconnected-(U1-SPK_P-Pad22)") (class "Default")
      (node (ref "U1") (pin "22") (pinfunction "SPK_P_22") (pintype "passive"))
    )
    (net (code "97") (name "unconnected-(U1-UART_CTS-Pad67)") (class "Default")
      (node (ref "U1") (pin "67") (pinfunction "UART_CTS_67") (pintype "passive"))
    )
    (net (code "98") (name "unconnected-(U1-UART_DCD-Pad70)") (class "Default")
      (node (ref "U1") (pin "70") (pinfunction "UART_DCD_70") (pintype "passive"))
    )
    (net (code "99") (name "unconnected-(U1-UART_DTR-Pad72)") (class "Default")
      (node (ref "U1") (pin "72") (pinfunction "UART_DTR_72") (pintype "passive"))
    )
    (net (code "100") (name "unconnected-(U1-UART_RI-Pad69)") (class "Default")
      (node (ref "U1") (pin "69") (pinfunction "UART_RI_69") (pintype "passive"))
    )
    (net (code "101") (name "unconnected-(U1-UART_RTS-Pad66)") (class "Default")
      (node (ref "U1") (pin "66") (pinfunction "UART_RTS_66") (pintype "passive"))
    )
    (net (code "102") (name "unconnected-(U2-BOOT0-Pad60)") (class "Default")
      (node (ref "U2") (pin "60") (pinfunction "BOOT0_60") (pintype "passive"))
    )
    (net (code "103") (name "unconnected-(U2-PA0-Pad14)") (class "Default")
      (node (ref "U2") (pin "14") (pinfunction "PA0_14") (pintype "passive"))
    )
    (net (code "104") (name "unconnected-(U2-PA1-Pad15)") (class "Default")
      (node (ref "U2") (pin "15") (pinfunction "PA1_15") (pintype "passive"))
    )
    (net (code "105") (name "unconnected-(U2-PA4-Pad20)") (class "Default")
      (node (ref "U2") (pin "20") (pinfunction "PA4_20") (pintype "passive"))
    )
    (net (code "106") (name "unconnected-(U2-PA5-Pad21)") (class "Default")
      (node (ref "U2") (pin "21") (pinfunction "PA5_21") (pintype "passive"))
    )
    (net (code "107") (name "unconnected-(U2-PA6-Pad22)") (class "Default")
      (node (ref "U2") (pin "22") (pinfunction "PA6_22") (pintype "passive"))
    )
    (net (code "108") (name "unconnected-(U2-PA7-Pad23)") (class "Default")
      (node (ref "U2") (pin "23") (pinfunction "PA7_23") (pintype "passive"))
    )
    (net (code "109") (name "unconnected-(U2-PA9-Pad42)") (class "Default")
      (node (ref "U2") (pin "42") (pinfunction "PA9_42") (pintype "passive"))
    )
    (net (code "110") (name "unconnected-(U2-PA10-Pad43)") (class "Default")
      (node (ref "U2") (pin "43") (pinfunction "PA10_43") (pintype "passive"))
    )
    (net (code "111") (name "unconnected-(U2-PA11-Pad44)") (class "Default")
      (node (ref "U2") (pin "44") (pinfunction "PA11_44") (pintype "passive"))
    )
    (net (code "112") (name "unconnected-(U2-PA12-Pad45)") (class "Default")
      (node (ref "U2") (pin "45") (pinfunction "PA12_45") (pintype "passive"))
    )
    (net (code "113") (name "unconnected-(U2-PA15-Pad50)") (class "Default")
      (node (ref "U2") (pin "50") (pinfunction "PA15_50") (pintype "passive"))
    )
    (net (code "114") (name "unconnected-(U2-PB3-Pad55)") (class "Default")
      (node (ref "U2") (pin "55") (pinfunction "PB3_55") (pintype "passive"))
    )
    (net (code "115") (name "unconnected-(U2-PB4-Pad56)") (class "Default")
      (node (ref "U2") (pin "56") (pinfunction "PB4_56") (pintype "passive"))
    )
    (net (code "116") (name "unconnected-(U2-PB5-Pad57)") (class "Default")
      (node (ref "U2") (pin "57") (pinfunction "PB5_57") (pintype "passive"))
    )
    (net (code "117") (name "unconnected-(U2-PB10-Pad29)") (class "Default")
      (node (ref "U2") (pin "29") (pinfunction "PB10_29") (pintype "passive"))
    )
    (net (code "118") (name "unconnected-(U2-PB11-Pad54)") (class "Default")
      (node (ref "U2") (pin "54") (pinfunction "PB11_54") (pintype "passive"))
    )
    (net (code "119") (name "unconnected-(U2-PC0-Pad8)") (class "Default")
      (node (ref "U2") (pin "8") (pinfunction "PC0_8") (pintype "passive"))
    )
    (net (code "120") (name "unconnected-(U2-PC1-Pad9)") (class "Default")
      (node (ref "U2") (pin "9") (pinfunction "PC1_9") (pintype "passive"))
    )
    (net (code "121") (name "unconnected-(U2-PC3-Pad11)") (class "Default")
      (node (ref "U2") (pin "11") (pinfunction "PC3_11") (pintype "passive"))
    )
    (net (code "122") (name "unconnected-(U2-PC6-Pad25)") (class "Default")
      (node (ref "U2") (pin "25") (pinfunction "PC6_25") (pintype "passive"))
    )
    (net (code "123") (name "unconnected-(U2-PC6-Pad37)") (class "Default")
      (node (ref "U2") (pin "37") (pinfunction "PC6_37") (pintype "passive"))
    )
    (net (code "124") (name "unconnected-(U2-PC7-Pad38)") (class "Default")
      (node (ref "U2") (pin "38") (pinfunction "PC7_38") (pintype "passive"))
    )
    (net (code "125") (name "unconnected-(U2-PC9-Pad40)") (class "Default")
      (node (ref "U2") (pin "40") (pinfunction "PC9_40") (pintype "passive"))
    )
    (net (code "126") (name "unconnected-(U2-PC10-Pad51)") (class "Default")
      (node (ref "U2") (pin "51") (pinfunction "PC10_51") (pintype "passive"))
    )
    (net (code "127") (name "unconnected-(U2-PC11-Pad52)") (class "Default")
      (node (ref "U2") (pin "52") (pinfunction "PC11_52") (pintype "passive"))
    )
    (net (code "128") (name "unconnected-(U2-PC12-Pad53)") (class "Default")
      (node (ref "U2") (pin "53") (pinfunction "PC12_53") (pintype "passive"))
    )
    (net (code "129") (name "unconnected-(U2-PC13-Pad2)") (class "Default")
      (node (ref "U2") (pin "2") (pinfunction "PC13_2") (pintype "passive"))
    )
    (net (code "130") (name "unconnected-(U2-PC14-OSC32_IN-Pad3)") (class "Default")
      (node (ref "U2") (pin "3") (pinfunction "PC14-OSC32_IN_3") (pintype "passive"))
    )
    (net (code "131") (name "unconnected-(U2-PC15-OSC32_OUT-Pad4)") (class "Default")
      (node (ref "U2") (pin "4") (pinfunction "PC15-OSC32_OUT_4") (pintype "passive"))
    )
    (net (code "132") (name "unconnected-(U2-VBAT-Pad1)") (class "Default")
      (node (ref "U2") (pin "1") (pinfunction "VBAT_1") (pintype "passive"))
    )
    (net (code "133") (name "unconnected-(U5-K2-Pad3)") (class "Default")
      (node (ref "U5") (pin "3") (pinfunction "K2_3") (pintype "passive"))
    )
    (net (code "134") (name "unconnected-(USB1-PadID)") (class "Default")
      (node (ref "USB1") (pin "ID") (pinfunction "ID_ID") (pintype "passive"))
    )
    (net (code "135") (name "unconnected-(X3-C6-VPP-Pad4)") (class "Default")
      (node (ref "X3") (pin "4") (pinfunction "C6-VPP_4") (pintype "passive"))
    )
  )
)
